# BreakoutTRRS-V0-2.net
KiCad netlist of a schematic drawn in EAGLE
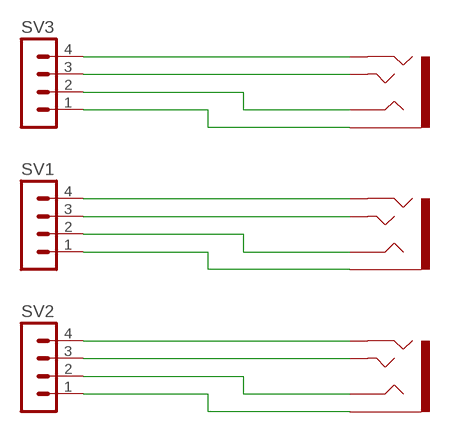
[diagram p0: schematic, sheet 1]

(export (version "E")
  (design (tool "Eeschema 10.0.6"))
  (components
    (comp (ref "SV1")
      (value "MA04-1")
      (footprint "eagle-import:MA04-1")
      (libsource (lib "eagle-import") (part "MA04-1"))
    )
    (comp (ref "SV2")
      (value "MA04-1")
      (footprint "eagle-import:MA04-1")
      (libsource (lib "eagle-import") (part "MA04-1"))
    )
    (comp (ref "SV3")
      (value "MA04-1")
      (footprint "eagle-import:MA04-1")
      (libsource (lib "eagle-import") (part "MA04-1"))
    )
    (comp (ref "TO-HEADSET1")
      (value "AUDIO-JACK3")
      (footprint "eagle-import:AUDIO-JACK-TRRS-SMD")
      (libsource (lib "eagle-import") (part "AUDIO-JACK3"))
    )
    (comp (ref "TO-HEADSET2")
      (value "AUDIO-JACK3")
      (footprint "eagle-import:AUDIO-JACK-TRRS-SMD")
      (libsource (lib "eagle-import") (part "AUDIO-JACK3"))
    )
    (comp (ref "TO-HEADSET3")
      (value "AUDIO-JACK3")
      (footprint "eagle-import:AUDIO-JACK-TRRS-SMD")
      (libsource (lib "eagle-import") (part "AUDIO-JACK3"))
    )
  )
  (nets
    (net (code "1") (name "Net-(SV1-Pad1)") (class "Default")
      (node (ref "SV1") (pin "1") (pinfunction "1_1") (pintype "passive"))
      (node (ref "TO-HEADSET2") (pin "EARTH") (pinfunction "EARTH_EARTH") (pintype "bidirectional"))
    )
    (net (code "2") (name "Net-(SV1-Pad2)") (class "Default")
      (node (ref "SV1") (pin "2") (pinfunction "2_2") (pintype "passive"))
      (node (ref "TO-HEADSET2") (pin "RING1") (pinfunction "RING1_RING1") (pintype "bidirectional"))
    )
    (net (code "3") (name "Net-(SV1-Pad3)") (class "Default")
      (node (ref "SV1") (pin "3") (pinfunction "3_3") (pintype "passive"))
      (node (ref "TO-HEADSET2") (pin "TIP") (pinfunction "TIP_TIP") (pintype "bidirectional"))
    )
    (net (code "4") (name "Net-(SV1-Pad4)") (class "Default")
      (node (ref "SV1") (pin "4") (pinfunction "4_4") (pintype "passive"))
      (node (ref "TO-HEADSET2") (pin "RING2") (pinfunction "RING2_RING2") (pintype "bidirectional"))
    )
    (net (code "5") (name "Net-(SV2-Pad1)") (class "Default")
      (node (ref "SV2") (pin "1") (pinfunction "1_1") (pintype "passive"))
      (node (ref "TO-HEADSET1") (pin "EARTH") (pinfunction "EARTH_EARTH") (pintype "bidirectional"))
    )
    (net (code "6") (name "Net-(SV2-Pad2)") (class "Default")
      (node (ref "SV2") (pin "2") (pinfunction "2_2") (pintype "passive"))
      (node (ref "TO-HEADSET1") (pin "RING1") (pinfunction "RING1_RING1") (pintype "bidirectional"))
    )
    (net (code "7") (name "Net-(SV2-Pad3)") (class "Default")
      (node (ref "SV2") (pin "3") (pinfunction "3_3") (pintype "passive"))
      (node (ref "TO-HEADSET1") (pin "TIP") (pinfunction "TIP_TIP") (pintype "bidirectional"))
    )
    (net (code "8") (name "Net-(SV2-Pad4)") (class "Default")
      (node (ref "SV2") (pin "4") (pinfunction "4_4") (pintype "passive"))
      (node (ref "TO-HEADSET1") (pin "RING2") (pinfunction "RING2_RING2") (pintype "bidirectional"))
    )
    (net (code "9") (name "Net-(SV3-Pad1)") (class "Default")
      (node (ref "SV3") (pin "1") (pinfunction "1_1") (pintype "passive"))
      (node (ref "TO-HEADSET3") (pin "EARTH") (pinfunction "EARTH_EARTH") (pintype "bidirectional"))
    )
    (net (code "10") (name "Net-(SV3-Pad2)") (class "Default")
      (node (ref "SV3") (pin "2") (pinfunction "2_2") (pintype "passive"))
      (node (ref "TO-HEADSET3") (pin "RING1") (pinfunction "RING1_RING1") (pintype "bidirectional"))
    )
    (net (code "11") (name "Net-(SV3-Pad3)") (class "Default")
      (node (ref "SV3") (pin "3") (pinfunction "3_3") (pintype "passive"))
      (node (ref "TO-HEADSET3") (pin "TIP") (pinfunction "TIP_TIP") (pintype "bidirectional"))
    )
    (net (code "12") (name "Net-(SV3-Pad4)") (class "Default")
      (node (ref "SV3") (pin "4") (pinfunction "4_4") (pintype "passive"))
      (node (ref "TO-HEADSET3") (pin "RING2") (pinfunction "RING2_RING2") (pintype "bidirectional"))
    )
  )
)
